# labproject.net
KiCad netlist of a schematic drawn in EAGLE
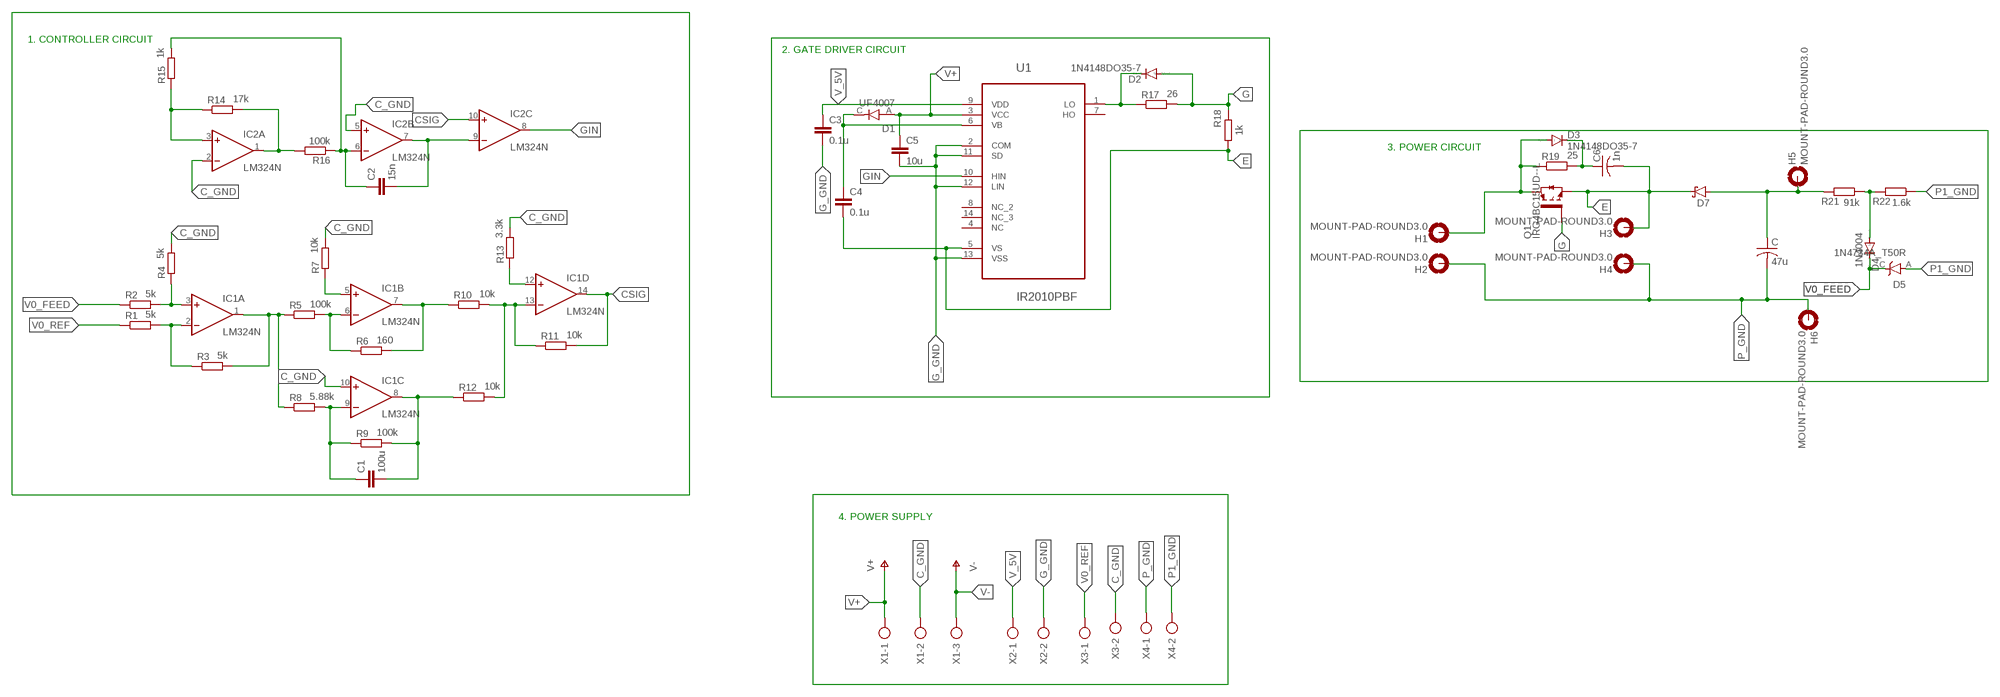
[diagram p0: schematic, sheet 1]

(export (version "E")
  (design (tool "Eeschema 10.0.6"))
  (components
    (comp (ref "C")
      (value "47u")
      (footprint "eagle-import:C075-032X103")
      (libsource (lib "eagle-import") (part "C-US075-032X103"))
    )
    (comp (ref "C1")
      (value "100u")
      (footprint "eagle-import:C025-024X044")
      (libsource (lib "eagle-import") (part "C-EU025-024X044"))
    )
    (comp (ref "C2")
      (value "15n")
      (footprint "eagle-import:C025-024X044")
      (libsource (lib "eagle-import") (part "C-EU025-024X044"))
    )
    (comp (ref "C3")
      (value "0.1u")
      (footprint "eagle-import:C025-024X044")
      (libsource (lib "eagle-import") (part "C-EU025-024X044"))
    )
    (comp (ref "C4")
      (value "0.1u")
      (footprint "eagle-import:C025-024X044")
      (libsource (lib "eagle-import") (part "C-EU025-024X044"))
    )
    (comp (ref "C5")
      (value "10u")
      (footprint "eagle-import:C025-024X044")
      (libsource (lib "eagle-import") (part "C-EU025-024X044"))
    )
    (comp (ref "C6")
      (value "1n")
      (footprint "eagle-import:C075-032X103")
      (libsource (lib "eagle-import") (part "C-US075-032X103"))
    )
    (comp (ref "D1")
      (value "UF4007")
      (footprint "eagle-import:DIOAD1055W87L533D272")
      (fields (field (name "MF") "ON Semiconductor"))
      (libsource (lib "eagle-import") (part "UF4007"))
    )
    (comp (ref "D2")
      (value "1N4148DO35-7")
      (footprint "eagle-import:DO35-7")
      (libsource (lib "eagle-import") (part "1N4148DO35-7"))
    )
    (comp (ref "D3")
      (value "1N4148DO35-7")
      (footprint "eagle-import:DO35-7")
      (libsource (lib "eagle-import") (part "1N4148DO35-7"))
    )
    (comp (ref "D4")
      (value "1N4004")
      (footprint "eagle-import:DO41-10")
      (libsource (lib "eagle-import") (part "1N4004"))
    )
    (comp (ref "D5")
      (value "1N4734A_T50R")
      (footprint "eagle-import:DIOAD1070W78L463D238P")
      (fields (field (name "MF") "ON Semiconductor"))
      (libsource (lib "eagle-import") (part "1N4734A_T50R"))
    )
    (comp (ref "D7")
      (value "SCHOTTKY-DIODEDO201T15")
      (footprint "eagle-import:DO201T15")
      (libsource (lib "eagle-import") (part "SCHOTTKY-DIODEDO201T15"))
    )
    (comp (ref "H1")
      (value "MOUNT-PAD-ROUND3.0")
      (footprint "eagle-import:3,0-PAD")
      (libsource (lib "eagle-import") (part "MOUNT-PAD-ROUND3.0"))
    )
    (comp (ref "H2")
      (value "MOUNT-PAD-ROUND3.0")
      (footprint "eagle-import:3,0-PAD")
      (libsource (lib "eagle-import") (part "MOUNT-PAD-ROUND3.0"))
    )
    (comp (ref "H3")
      (value "MOUNT-PAD-ROUND3.0")
      (footprint "eagle-import:3,0-PAD")
      (libsource (lib "eagle-import") (part "MOUNT-PAD-ROUND3.0"))
    )
    (comp (ref "H4")
      (value "MOUNT-PAD-ROUND3.0")
      (footprint "eagle-import:3,0-PAD")
      (libsource (lib "eagle-import") (part "MOUNT-PAD-ROUND3.0"))
    )
    (comp (ref "H5")
      (value "MOUNT-PAD-ROUND3.0")
      (footprint "eagle-import:3,0-PAD")
      (libsource (lib "eagle-import") (part "MOUNT-PAD-ROUND3.0"))
    )
    (comp (ref "H6")
      (value "MOUNT-PAD-ROUND3.0")
      (footprint "eagle-import:3,0-PAD")
      (libsource (lib "eagle-import") (part "MOUNT-PAD-ROUND3.0"))
    )
    (comp (ref "IC1")
      (value "LM324N")
      (footprint "eagle-import:DIL14")
      (libsource (lib "eagle-import") (part "LM324N"))
    )
    (comp (ref "IC2")
      (value "LM324N")
      (footprint "eagle-import:DIL14")
      (libsource (lib "eagle-import") (part "LM324N"))
    )
    (comp (ref "Q1")
      (value "IRG4BC15UD--L")
      (footprint "eagle-import:TO262-V")
      (fields (field (name "MF") "Infineon") (field (name "MP") "IRG4BC15UD"))
      (libsource (lib "eagle-import") (part "IRG4BC15UD--L"))
    )
    (comp (ref "R1")
      (value "5k")
      (footprint "eagle-import:0204_7")
      (libsource (lib "eagle-import") (part "R-EU_0204/7"))
    )
    (comp (ref "R2")
      (value "5k")
      (footprint "eagle-import:0204_7")
      (libsource (lib "eagle-import") (part "R-EU_0204/7"))
    )
    (comp (ref "R3")
      (value "5k")
      (footprint "eagle-import:0204_7")
      (libsource (lib "eagle-import") (part "R-EU_0204/7"))
    )
    (comp (ref "R4")
      (value "5k")
      (footprint "eagle-import:0204_7")
      (libsource (lib "eagle-import") (part "R-EU_0204/7"))
    )
    (comp (ref "R5")
      (value "100k")
      (footprint "eagle-import:0204_7")
      (libsource (lib "eagle-import") (part "R-EU_0204/7"))
    )
    (comp (ref "R6")
      (value "160")
      (footprint "eagle-import:0204_7")
      (libsource (lib "eagle-import") (part "R-EU_0204/7"))
    )
    (comp (ref "R7")
      (value "10k")
      (footprint "eagle-import:0204_7")
      (libsource (lib "eagle-import") (part "R-EU_0204/7"))
    )
    (comp (ref "R8")
      (value "5.88k")
      (footprint "eagle-import:0204_7")
      (libsource (lib "eagle-import") (part "R-EU_0204/7"))
    )
    (comp (ref "R9")
      (value "100k")
      (footprint "eagle-import:0204_7")
      (libsource (lib "eagle-import") (part "R-EU_0204/7"))
    )
    (comp (ref "R10")
      (value "10k")
      (footprint "eagle-import:0204_7")
      (libsource (lib "eagle-import") (part "R-EU_0204/7"))
    )
    (comp (ref "R11")
      (value "10k")
      (footprint "eagle-import:0204_7")
      (libsource (lib "eagle-import") (part "R-EU_0204/7"))
    )
    (comp (ref "R12")
      (value "10k")
      (footprint "eagle-import:0204_7")
      (libsource (lib "eagle-import") (part "R-EU_0204/7"))
    )
    (comp (ref "R13")
      (value "3.3k")
      (footprint "eagle-import:0204_7")
      (libsource (lib "eagle-import") (part "R-EU_0204/7"))
    )
    (comp (ref "R14")
      (value "17k")
      (footprint "eagle-import:0204_7")
      (libsource (lib "eagle-import") (part "R-EU_0204/7"))
    )
    (comp (ref "R15")
      (value "1k")
      (footprint "eagle-import:0204_7")
      (libsource (lib "eagle-import") (part "R-EU_0204/7"))
    )
    (comp (ref "R16")
      (value "100k")
      (footprint "eagle-import:0204_7")
      (libsource (lib "eagle-import") (part "R-EU_0204/7"))
    )
    (comp (ref "R17")
      (value "26")
      (footprint "eagle-import:0204_7")
      (libsource (lib "eagle-import") (part "R-EU_0204/7"))
    )
    (comp (ref "R18")
      (value "1k")
      (footprint "eagle-import:0204_7")
      (libsource (lib "eagle-import") (part "R-EU_0204/7"))
    )
    (comp (ref "R19")
      (value "25")
      (footprint "eagle-import:0204_7")
      (libsource (lib "eagle-import") (part "R-EU_0204/7"))
    )
    (comp (ref "R21")
      (value "91k")
      (footprint "eagle-import:0204_7")
      (libsource (lib "eagle-import") (part "R-EU_0204/7"))
    )
    (comp (ref "R22")
      (value "1.6k")
      (footprint "eagle-import:0204_7")
      (libsource (lib "eagle-import") (part "R-EU_0204/7"))
    )
    (comp (ref "U1")
      (value "IR2010PBF")
      (footprint "eagle-import:DIP254P762X533-14")
      (fields (field (name "MF") "Infineon Technologies"))
      (libsource (lib "eagle-import") (part "IR2010PBF"))
    )
    (comp (ref "X1")
      (value "AK300/3")
      (footprint "eagle-import:AK300_3")
      (libsource (lib "eagle-import") (part "AK300/3"))
    )
    (comp (ref "X2")
      (value "AK300/2")
      (footprint "eagle-import:AK300_2")
      (libsource (lib "eagle-import") (part "AK300/2"))
    )
    (comp (ref "X3")
      (value "AK300/2")
      (footprint "eagle-import:AK300_2")
      (libsource (lib "eagle-import") (part "AK300/2"))
    )
    (comp (ref "X4")
      (value "AK300/2")
      (footprint "eagle-import:AK300_2")
      (libsource (lib "eagle-import") (part "AK300/2"))
    )
  )
  (nets
    (net (code "1") (name "CSIG") (class "Default")
      (node (ref "IC1") (pin "14") (pinfunction "OUT_14") (pintype "output"))
      (node (ref "IC2") (pin "10") (pinfunction "+IN_10") (pintype "input"))
      (node (ref "R11") (pin "2") (pinfunction "2_2") (pintype "passive"))
    )
    (net (code "2") (name "C_GND") (class "Default")
      (node (ref "IC1") (pin "10") (pinfunction "+IN_10") (pintype "input"))
      (node (ref "IC2") (pin "2") (pinfunction "-IN_2") (pintype "input"))
      (node (ref "IC2") (pin "5") (pinfunction "+IN_5") (pintype "input"))
      (node (ref "R13") (pin "2") (pinfunction "2_2") (pintype "passive"))
      (node (ref "R4") (pin "2") (pinfunction "2_2") (pintype "passive"))
      (node (ref "R7") (pin "2") (pinfunction "2_2") (pintype "passive"))
      (node (ref "X1") (pin "2") (pinfunction "KL_2") (pintype "passive"))
      (node (ref "X3") (pin "2") (pinfunction "KL_2") (pintype "passive"))
    )
    (net (code "3") (name "E") (class "Default")
      (node (ref "C4") (pin "2") (pinfunction "2_2") (pintype "passive"))
      (node (ref "C6") (pin "2") (pinfunction "2_2") (pintype "passive"))
      (node (ref "D7") (pin "C") (pinfunction "C_C") (pintype "passive"))
      (node (ref "H3") (pin "B3,0") (pinfunction "MOUNT_B3,0") (pintype "passive"))
      (node (ref "Q1") (pin "3") (pinfunction "E_3") (pintype "passive"))
      (node (ref "R18") (pin "2") (pinfunction "2_2") (pintype "passive"))
      (node (ref "U1") (pin "5") (pinfunction "VS_5") (pintype "power_in"))
    )
    (net (code "4") (name "G") (class "Default")
      (node (ref "D2") (pin "A") (pinfunction "A_A") (pintype "passive"))
      (node (ref "Q1") (pin "1") (pinfunction "G_1") (pintype "passive"))
      (node (ref "R17") (pin "2") (pinfunction "2_2") (pintype "passive"))
      (node (ref "R18") (pin "1") (pinfunction "1_1") (pintype "passive"))
    )
    (net (code "5") (name "GIN") (class "Default")
      (node (ref "IC2") (pin "8") (pinfunction "OUT_8") (pintype "output"))
      (node (ref "U1") (pin "10") (pinfunction "HIN_10") (pintype "input"))
    )
    (net (code "6") (name "G_GND") (class "Default")
      (node (ref "C3") (pin "2") (pinfunction "2_2") (pintype "passive"))
      (node (ref "C5") (pin "2") (pinfunction "2_2") (pintype "passive"))
      (node (ref "U1") (pin "11") (pinfunction "SD_11") (pintype "input"))
      (node (ref "U1") (pin "12") (pinfunction "LIN_12") (pintype "input"))
      (node (ref "U1") (pin "13") (pinfunction "VSS_13") (pintype "power_in"))
      (node (ref "U1") (pin "2") (pinfunction "COM_2") (pintype "passive"))
      (node (ref "X2") (pin "2") (pinfunction "KL_2") (pintype "passive"))
    )
    (net (code "7") (name "Net-(C6-Pad1)") (class "Default")
      (node (ref "C6") (pin "1") (pinfunction "1_1") (pintype "passive"))
      (node (ref "D3") (pin "C") (pinfunction "C_C") (pintype "passive"))
      (node (ref "R19") (pin "2") (pinfunction "2_2") (pintype "passive"))
    )
    (net (code "8") (name "Net-(D1-K)") (class "Default")
      (node (ref "C4") (pin "1") (pinfunction "1_1") (pintype "passive"))
      (node (ref "D1") (pin "C") (pinfunction "K_C") (pintype "passive"))
      (node (ref "U1") (pin "6") (pinfunction "VB_6") (pintype "power_in"))
    )
    (net (code "9") (name "Net-(D4-PadA)") (class "Default")
      (node (ref "D4") (pin "A") (pinfunction "A_A") (pintype "passive"))
      (node (ref "R21") (pin "1") (pinfunction "1_1") (pintype "passive"))
      (node (ref "R22") (pin "2") (pinfunction "2_2") (pintype "passive"))
    )
    (net (code "10") (name "Net-(H1-MOUNT)") (class "Default")
      (node (ref "D3") (pin "A") (pinfunction "A_A") (pintype "passive"))
      (node (ref "H1") (pin "B3,0") (pinfunction "MOUNT_B3,0") (pintype "passive"))
      (node (ref "Q1") (pin "2") (pinfunction "C_2") (pintype "passive"))
      (node (ref "R19") (pin "1") (pinfunction "1_1") (pintype "passive"))
    )
    (net (code "11") (name "Net-(H5-MOUNT)") (class "Default")
      (node (ref "C") (pin "1") (pinfunction "1_1") (pintype "passive"))
      (node (ref "D7") (pin "A") (pinfunction "A_A") (pintype "passive"))
      (node (ref "H5") (pin "B3,0") (pinfunction "MOUNT_B3,0") (pintype "passive"))
      (node (ref "R21") (pin "2") (pinfunction "2_2") (pintype "passive"))
    )
    (net (code "12") (name "Net-(IC1A-+IN)") (class "Default")
      (node (ref "IC1") (pin "3") (pinfunction "+IN_3") (pintype "input"))
      (node (ref "R2") (pin "2") (pinfunction "2_2") (pintype "passive"))
      (node (ref "R4") (pin "1") (pinfunction "1_1") (pintype "passive"))
    )
    (net (code "13") (name "Net-(IC1A--IN)") (class "Default")
      (node (ref "IC1") (pin "2") (pinfunction "-IN_2") (pintype "input"))
      (node (ref "R1") (pin "2") (pinfunction "2_2") (pintype "passive"))
      (node (ref "R3") (pin "1") (pinfunction "1_1") (pintype "passive"))
    )
    (net (code "14") (name "Net-(IC1A-OUT)") (class "Default")
      (node (ref "IC1") (pin "1") (pinfunction "OUT_1") (pintype "output"))
      (node (ref "R3") (pin "2") (pinfunction "2_2") (pintype "passive"))
      (node (ref "R5") (pin "1") (pinfunction "1_1") (pintype "passive"))
      (node (ref "R8") (pin "1") (pinfunction "1_1") (pintype "passive"))
    )
    (net (code "15") (name "Net-(IC1B-+IN)") (class "Default")
      (node (ref "IC1") (pin "5") (pinfunction "+IN_5") (pintype "input"))
      (node (ref "R7") (pin "1") (pinfunction "1_1") (pintype "passive"))
    )
    (net (code "16") (name "Net-(IC1B--IN)") (class "Default")
      (node (ref "IC1") (pin "6") (pinfunction "-IN_6") (pintype "input"))
      (node (ref "R5") (pin "2") (pinfunction "2_2") (pintype "passive"))
      (node (ref "R6") (pin "1") (pinfunction "1_1") (pintype "passive"))
    )
    (net (code "17") (name "Net-(IC1B-OUT)") (class "Default")
      (node (ref "IC1") (pin "7") (pinfunction "OUT_7") (pintype "output"))
      (node (ref "R10") (pin "1") (pinfunction "1_1") (pintype "passive"))
      (node (ref "R6") (pin "2") (pinfunction "2_2") (pintype "passive"))
    )
    (net (code "18") (name "Net-(IC1C--IN)") (class "Default")
      (node (ref "C1") (pin "1") (pinfunction "1_1") (pintype "passive"))
      (node (ref "IC1") (pin "9") (pinfunction "-IN_9") (pintype "input"))
      (node (ref "R8") (pin "2") (pinfunction "2_2") (pintype "passive"))
      (node (ref "R9") (pin "1") (pinfunction "1_1") (pintype "passive"))
    )
    (net (code "19") (name "Net-(IC1C-OUT)") (class "Default")
      (node (ref "C1") (pin "2") (pinfunction "2_2") (pintype "passive"))
      (node (ref "IC1") (pin "8") (pinfunction "OUT_8") (pintype "output"))
      (node (ref "R12") (pin "1") (pinfunction "1_1") (pintype "passive"))
      (node (ref "R9") (pin "2") (pinfunction "2_2") (pintype "passive"))
    )
    (net (code "20") (name "Net-(IC1D-+IN)") (class "Default")
      (node (ref "IC1") (pin "12") (pinfunction "+IN_12") (pintype "input"))
      (node (ref "R13") (pin "1") (pinfunction "1_1") (pintype "passive"))
    )
    (net (code "21") (name "Net-(IC1D--IN)") (class "Default")
      (node (ref "IC1") (pin "13") (pinfunction "-IN_13") (pintype "input"))
      (node (ref "R10") (pin "2") (pinfunction "2_2") (pintype "passive"))
      (node (ref "R11") (pin "1") (pinfunction "1_1") (pintype "passive"))
      (node (ref "R12") (pin "2") (pinfunction "2_2") (pintype "passive"))
    )
    (net (code "22") (name "Net-(IC2A-+IN)") (class "Default")
      (node (ref "IC2") (pin "3") (pinfunction "+IN_3") (pintype "input"))
      (node (ref "R14") (pin "1") (pinfunction "1_1") (pintype "passive"))
      (node (ref "R15") (pin "1") (pinfunction "1_1") (pintype "passive"))
    )
    (net (code "23") (name "Net-(IC2A-OUT)") (class "Default")
      (node (ref "IC2") (pin "1") (pinfunction "OUT_1") (pintype "output"))
      (node (ref "R14") (pin "2") (pinfunction "2_2") (pintype "passive"))
      (node (ref "R16") (pin "2") (pinfunction "2_2") (pintype "passive"))
    )
    (net (code "24") (name "Net-(IC2B--IN)") (class "Default")
      (node (ref "C2") (pin "1") (pinfunction "1_1") (pintype "passive"))
      (node (ref "IC2") (pin "6") (pinfunction "-IN_6") (pintype "input"))
      (node (ref "R15") (pin "2") (pinfunction "2_2") (pintype "passive"))
      (node (ref "R16") (pin "1") (pinfunction "1_1") (pintype "passive"))
    )
    (net (code "25") (name "Net-(IC2B-OUT)") (class "Default")
      (node (ref "C2") (pin "2") (pinfunction "2_2") (pintype "passive"))
      (node (ref "IC2") (pin "7") (pinfunction "OUT_7") (pintype "output"))
      (node (ref "IC2") (pin "9") (pinfunction "-IN_9") (pintype "input"))
    )
    (net (code "26") (name "Net-(U1-LO)") (class "Default")
      (node (ref "D2") (pin "C") (pinfunction "C_C") (pintype "passive"))
      (node (ref "R17") (pin "1") (pinfunction "1_1") (pintype "passive"))
      (node (ref "U1") (pin "1") (pinfunction "LO_1") (pintype "output"))
    )
    (net (code "27") (name "P1_GND") (class "Default")
      (node (ref "D5") (pin "A") (pinfunction "A_A") (pintype "passive"))
      (node (ref "R22") (pin "1") (pinfunction "1_1") (pintype "passive"))
      (node (ref "X4") (pin "2") (pinfunction "KL_2") (pintype "passive"))
    )
    (net (code "28") (name "P_GND") (class "Default")
      (node (ref "C") (pin "2") (pinfunction "2_2") (pintype "passive"))
      (node (ref "H2") (pin "B3,0") (pinfunction "MOUNT_B3,0") (pintype "passive"))
      (node (ref "H4") (pin "B3,0") (pinfunction "MOUNT_B3,0") (pintype "passive"))
      (node (ref "H6") (pin "B3,0") (pinfunction "MOUNT_B3,0") (pintype "passive"))
      (node (ref "X4") (pin "1") (pinfunction "KL_1") (pintype "passive"))
    )
    (net (code "29") (name "V+") (class "Default")
      (node (ref "C5") (pin "1") (pinfunction "1_1") (pintype "passive"))
      (node (ref "D1") (pin "A") (pinfunction "A_A") (pintype "passive"))
      (node (ref "U1") (pin "3") (pinfunction "VCC_3") (pintype "power_in"))
      (node (ref "X1") (pin "1") (pinfunction "KL_1") (pintype "passive"))
    )
    (net (code "30") (name "V-") (class "Default")
      (node (ref "X1") (pin "3") (pinfunction "KL_3") (pintype "passive"))
    )
    (net (code "31") (name "V0_FEED") (class "Default")
      (node (ref "D4") (pin "C") (pinfunction "C_C") (pintype "passive"))
      (node (ref "D5") (pin "C") (pinfunction "C_C") (pintype "passive"))
      (node (ref "R2") (pin "1") (pinfunction "1_1") (pintype "passive"))
    )
    (net (code "32") (name "V0_REF") (class "Default")
      (node (ref "R1") (pin "1") (pinfunction "1_1") (pintype "passive"))
      (node (ref "X3") (pin "1") (pinfunction "KL_1") (pintype "passive"))
    )
    (net (code "33") (name "V_5V") (class "Default")
      (node (ref "C3") (pin "1") (pinfunction "1_1") (pintype "passive"))
      (node (ref "U1") (pin "9") (pinfunction "VDD_9") (pintype "power_in"))
      (node (ref "X2") (pin "1") (pinfunction "KL_1") (pintype "passive"))
    )
    (net (code "34") (name "unconnected-(U1-HO-Pad7)") (class "Default")
      (node (ref "U1") (pin "7") (pinfunction "HO_7") (pintype "output"))
    )
    (net (code "35") (name "unconnected-(U1-NC-Pad4)") (class "Default")
      (node (ref "U1") (pin "4") (pinfunction "NC_4") (pintype "no_connect"))
    )
    (net (code "36") (name "unconnected-(U1-NC_2-Pad8)") (class "Default")
      (node (ref "U1") (pin "8") (pinfunction "NC_2_8") (pintype "no_connect"))
    )
    (net (code "37") (name "unconnected-(U1-NC_3-Pad14)") (class "Default")
      (node (ref "U1") (pin "14") (pinfunction "NC_3_14") (pintype "no_connect"))
    )
  )
)
